# LTC3200-5_Breakout_Board.net
KiCad netlist of a schematic drawn in EAGLE
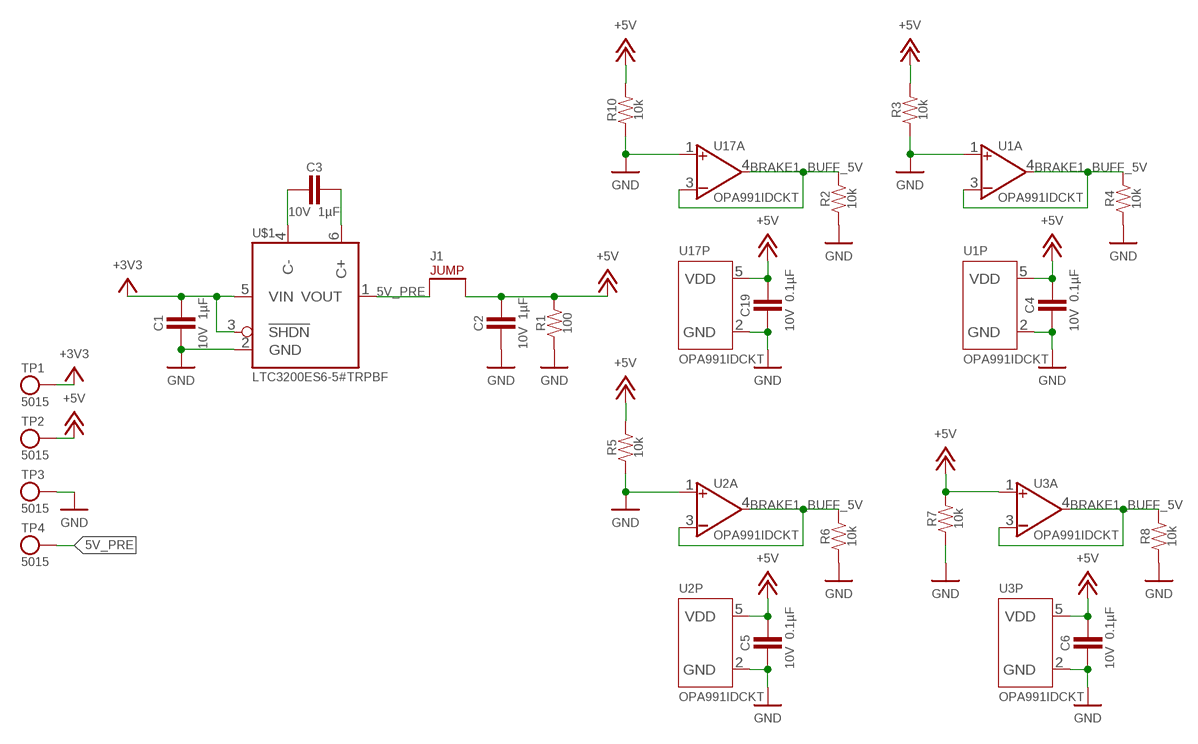
[diagram p0: schematic, sheet 1]

(export (version "E")
  (design (tool "Eeschema 10.0.6"))
  (components
    (comp (ref "C1")
      (value "CAPACITOR_0603_10V_1UF")
      (footprint "eagle-import:0603-CAP")
      (fields
        (field (name "CAPACITANCE") "1µF")
        (field (name "MANUFACTURER") "Yageo")
        (field (name "MPN") "CC0603KRX7R6BB105")
        (field (name "TOLERANCE") "10%")
        (field (name "VOLTAGE") "10V")
      )
      (libsource (lib "eagle-import") (part "CAPACITOR_?_060310V_1UF"))
    )
    (comp (ref "C2")
      (value "CAPACITOR_0603_10V_1UF")
      (footprint "eagle-import:0603-CAP")
      (fields
        (field (name "CAPACITANCE") "1µF")
        (field (name "MANUFACTURER") "Yageo")
        (field (name "MPN") "CC0603KRX7R6BB105")
        (field (name "TOLERANCE") "10%")
        (field (name "VOLTAGE") "10V")
      )
      (libsource (lib "eagle-import") (part "CAPACITOR_?_060310V_1UF"))
    )
    (comp (ref "C3")
      (value "CAPACITOR_0603_10V_1UF")
      (footprint "eagle-import:0603-CAP")
      (fields
        (field (name "CAPACITANCE") "1µF")
        (field (name "MANUFACTURER") "Yageo")
        (field (name "MPN") "CC0603KRX7R6BB105")
        (field (name "TOLERANCE") "10%")
        (field (name "VOLTAGE") "10V")
      )
      (libsource (lib "eagle-import") (part "CAPACITOR_?_060310V_1UF"))
    )
    (comp (ref "C4")
      (value "CAPACITOR_0603_10V_0.1UF")
      (footprint "eagle-import:0603-CAP")
      (fields
        (field (name "CAPACITANCE") "0.1µF")
        (field (name "MANUFACTURER") "Vishay Vitramon")
        (field (name "MPN") "VJ0603Y104JXQPW1BC")
        (field (name "TOLERANCE") "5%")
        (field (name "VOLTAGE") "10V")
      )
      (libsource (lib "eagle-import") (part "CAPACITOR_?_060310V_0.1UF"))
    )
    (comp (ref "C5")
      (value "CAPACITOR_0603_10V_0.1UF")
      (footprint "eagle-import:0603-CAP")
      (fields
        (field (name "CAPACITANCE") "0.1µF")
        (field (name "MANUFACTURER") "Vishay Vitramon")
        (field (name "MPN") "VJ0603Y104JXQPW1BC")
        (field (name "TOLERANCE") "5%")
        (field (name "VOLTAGE") "10V")
      )
      (libsource (lib "eagle-import") (part "CAPACITOR_?_060310V_0.1UF"))
    )
    (comp (ref "C6")
      (value "CAPACITOR_0603_10V_0.1UF")
      (footprint "eagle-import:0603-CAP")
      (fields
        (field (name "CAPACITANCE") "0.1µF")
        (field (name "MANUFACTURER") "Vishay Vitramon")
        (field (name "MPN") "VJ0603Y104JXQPW1BC")
        (field (name "TOLERANCE") "5%")
        (field (name "VOLTAGE") "10V")
      )
      (libsource (lib "eagle-import") (part "CAPACITOR_?_060310V_0.1UF"))
    )
    (comp (ref "C19")
      (value "CAPACITOR_0603_10V_0.1UF")
      (footprint "eagle-import:0603-CAP")
      (fields
        (field (name "CAPACITANCE") "0.1µF")
        (field (name "MANUFACTURER") "Vishay Vitramon")
        (field (name "MPN") "VJ0603Y104JXQPW1BC")
        (field (name "TOLERANCE") "5%")
        (field (name "VOLTAGE") "10V")
      )
      (libsource (lib "eagle-import") (part "CAPACITOR_?_060310V_0.1UF"))
    )
    (comp (ref "J1")
      (value "JUMPER_1X02_")
      (footprint "eagle-import:1X02")
      (libsource (lib "eagle-import") (part "JUMPER_?_1X02"))
    )
    (comp (ref "R1")
      (value "RESISTOR_0603_100")
      (footprint "eagle-import:0603-RES")
      (fields
        (field (name "MANUFACTURER") "Yageo")
        (field (name "MPN") "RC0603FR-07100RL")
        (field (name "POWER") "0.1W")
        (field (name "RESISTANCE") "100")
      )
      (libsource (lib "eagle-import") (part "RESISTOR_?_0603100"))
    )
    (comp (ref "R2")
      (value "RESISTOR_0603_10K")
      (footprint "eagle-import:0603-RES")
      (fields
        (field (name "MANUFACTURER") "Yageo")
        (field (name "MPN") "RC0603FR-0710KL")
        (field (name "POWER") "0.1W")
        (field (name "RESISTANCE") "10k")
      )
      (libsource (lib "eagle-import") (part "RESISTOR_?_060310K"))
    )
    (comp (ref "R3")
      (value "RESISTOR_0603_10K")
      (footprint "eagle-import:0603-RES")
      (fields
        (field (name "MANUFACTURER") "Yageo")
        (field (name "MPN") "RC0603FR-0710KL")
        (field (name "POWER") "0.1W")
        (field (name "RESISTANCE") "10k")
      )
      (libsource (lib "eagle-import") (part "RESISTOR_?_060310K"))
    )
    (comp (ref "R4")
      (value "RESISTOR_0603_10K")
      (footprint "eagle-import:0603-RES")
      (fields
        (field (name "MANUFACTURER") "Yageo")
        (field (name "MPN") "RC0603FR-0710KL")
        (field (name "POWER") "0.1W")
        (field (name "RESISTANCE") "10k")
      )
      (libsource (lib "eagle-import") (part "RESISTOR_?_060310K"))
    )
    (comp (ref "R5")
      (value "RESISTOR_0603_10K")
      (footprint "eagle-import:0603-RES")
      (fields
        (field (name "MANUFACTURER") "Yageo")
        (field (name "MPN") "RC0603FR-0710KL")
        (field (name "POWER") "0.1W")
        (field (name "RESISTANCE") "10k")
      )
      (libsource (lib "eagle-import") (part "RESISTOR_?_060310K"))
    )
    (comp (ref "R6")
      (value "RESISTOR_0603_10K")
      (footprint "eagle-import:0603-RES")
      (fields
        (field (name "MANUFACTURER") "Yageo")
        (field (name "MPN") "RC0603FR-0710KL")
        (field (name "POWER") "0.1W")
        (field (name "RESISTANCE") "10k")
      )
      (libsource (lib "eagle-import") (part "RESISTOR_?_060310K"))
    )
    (comp (ref "R7")
      (value "RESISTOR_0603_10K")
      (footprint "eagle-import:0603-RES")
      (fields
        (field (name "MANUFACTURER") "Yageo")
        (field (name "MPN") "RC0603FR-0710KL")
        (field (name "POWER") "0.1W")
        (field (name "RESISTANCE") "10k")
      )
      (libsource (lib "eagle-import") (part "RESISTOR_?_060310K"))
    )
    (comp (ref "R8")
      (value "RESISTOR_0603_10K")
      (footprint "eagle-import:0603-RES")
      (fields
        (field (name "MANUFACTURER") "Yageo")
        (field (name "MPN") "RC0603FR-0710KL")
        (field (name "POWER") "0.1W")
        (field (name "RESISTANCE") "10k")
      )
      (libsource (lib "eagle-import") (part "RESISTOR_?_060310K"))
    )
    (comp (ref "R10")
      (value "RESISTOR_0603_10K")
      (footprint "eagle-import:0603-RES")
      (fields
        (field (name "MANUFACTURER") "Yageo")
        (field (name "MPN") "RC0603FR-0710KL")
        (field (name "POWER") "0.1W")
        (field (name "RESISTANCE") "10k")
      )
      (libsource (lib "eagle-import") (part "RESISTOR_?_060310K"))
    )
    (comp (ref "TP1")
      (value "TEST_POINT")
      (footprint "eagle-import:MICRO_MINIATURE")
      (fields (field (name "MPN") "5015") (field (name "MANUFACTURER") "Keystone Electronics"))
      (libsource (lib "eagle-import") (part "TEST_POINT"))
    )
    (comp (ref "TP2")
      (value "TEST_POINT")
      (footprint "eagle-import:MICRO_MINIATURE")
      (fields (field (name "MPN") "5015") (field (name "MANUFACTURER") "Keystone Electronics"))
      (libsource (lib "eagle-import") (part "TEST_POINT"))
    )
    (comp (ref "TP3")
      (value "TEST_POINT")
      (footprint "eagle-import:MICRO_MINIATURE")
      (fields (field (name "MPN") "5015") (field (name "MANUFACTURER") "Keystone Electronics"))
      (libsource (lib "eagle-import") (part "TEST_POINT"))
    )
    (comp (ref "TP4")
      (value "TEST_POINT")
      (footprint "eagle-import:MICRO_MINIATURE")
      (fields (field (name "MPN") "5015") (field (name "MANUFACTURER") "Keystone Electronics"))
      (libsource (lib "eagle-import") (part "TEST_POINT"))
    )
    (comp (ref "U$1")
      (value "LTC3200-5")
      (footprint "eagle-import:SOT-23-6")
      (fields (field (name "MPN") "LTC3200ES6-5#TRPBF") (field (name "MANUFACTURER") "Analog Devices Inc."))
      (libsource (lib "eagle-import") (part "LTC3200-5"))
    )
    (comp (ref "U1")
      (value "OPAMP_1_CHANNEL_OPA991")
      (footprint "eagle-import:SC-70-5")
      (fields (field (name "MPN") "OPA991IDCKT"))
      (libsource (lib "eagle-import") (part "OPAMP_1_CHANNEL_OPA991"))
    )
    (comp (ref "U2")
      (value "OPAMP_1_CHANNEL_OPA991")
      (footprint "eagle-import:SC-70-5")
      (fields (field (name "MPN") "OPA991IDCKT"))
      (libsource (lib "eagle-import") (part "OPAMP_1_CHANNEL_OPA991"))
    )
    (comp (ref "U3")
      (value "OPAMP_1_CHANNEL_OPA991")
      (footprint "eagle-import:SC-70-5")
      (fields (field (name "MPN") "OPA991IDCKT"))
      (libsource (lib "eagle-import") (part "OPAMP_1_CHANNEL_OPA991"))
    )
    (comp (ref "U17")
      (value "OPAMP_1_CHANNEL_OPA991")
      (footprint "eagle-import:SC-70-5")
      (fields (field (name "MPN") "OPA991IDCKT"))
      (libsource (lib "eagle-import") (part "OPAMP_1_CHANNEL_OPA991"))
    )
  )
  (nets
    (net (code "1") (name "+3V3") (class "Default")
      (node (ref "C1") (pin "1") (pinfunction "1_1") (pintype "passive"))
      (node (ref "TP1") (pin "1") (pinfunction "P$1_1") (pintype "bidirectional"))
      (node (ref "U$1") (pin "3") (pinfunction "~{SHDN}_3") (pintype "input"))
      (node (ref "U$1") (pin "5") (pinfunction "VIN_5") (pintype "power_in"))
    )
    (net (code "2") (name "+5V") (class "Default")
      (node (ref "C19") (pin "1") (pinfunction "1_1") (pintype "passive"))
      (node (ref "C2") (pin "1") (pinfunction "1_1") (pintype "passive"))
      (node (ref "C4") (pin "1") (pinfunction "1_1") (pintype "passive"))
      (node (ref "C5") (pin "1") (pinfunction "1_1") (pintype "passive"))
      (node (ref "C6") (pin "1") (pinfunction "1_1") (pintype "passive"))
      (node (ref "J1") (pin "2") (pinfunction "P$2_2") (pintype "passive"))
      (node (ref "R1") (pin "2") (pinfunction "2_2") (pintype "passive"))
      (node (ref "R10") (pin "2") (pinfunction "2_2") (pintype "passive"))
      (node (ref "R3") (pin "2") (pinfunction "2_2") (pintype "passive"))
      (node (ref "R5") (pin "2") (pinfunction "2_2") (pintype "passive"))
      (node (ref "R7") (pin "2") (pinfunction "2_2") (pintype "passive"))
      (node (ref "TP2") (pin "1") (pinfunction "P$1_1") (pintype "bidirectional"))
      (node (ref "U1") (pin "5") (pinfunction "VDD_5") (pintype "power_in"))
      (node (ref "U17") (pin "5") (pinfunction "VDD_5") (pintype "power_in"))
      (node (ref "U2") (pin "5") (pinfunction "VDD_5") (pintype "power_in"))
      (node (ref "U3") (pin "1") (pinfunction "VIN+_1") (pintype "input"))
      (node (ref "U3") (pin "5") (pinfunction "VDD_5") (pintype "power_in"))
    )
    (net (code "3") (name "/BRAKE1_BUFF_5V") (class "Default")
      (node (ref "R2") (pin "2") (pinfunction "2_2") (pintype "passive"))
      (node (ref "R4") (pin "2") (pinfunction "2_2") (pintype "passive"))
      (node (ref "R6") (pin "2") (pinfunction "2_2") (pintype "passive"))
      (node (ref "R8") (pin "2") (pinfunction "2_2") (pintype "passive"))
      (node (ref "U1") (pin "3") (pinfunction "VIN-_3") (pintype "input"))
      (node (ref "U1") (pin "4") (pinfunction "VOUT_4") (pintype "output"))
      (node (ref "U17") (pin "3") (pinfunction "VIN-_3") (pintype "input"))
      (node (ref "U17") (pin "4") (pinfunction "VOUT_4") (pintype "output"))
      (node (ref "U2") (pin "3") (pinfunction "VIN-_3") (pintype "input"))
      (node (ref "U2") (pin "4") (pinfunction "VOUT_4") (pintype "output"))
      (node (ref "U3") (pin "3") (pinfunction "VIN-_3") (pintype "input"))
      (node (ref "U3") (pin "4") (pinfunction "VOUT_4") (pintype "output"))
    )
    (net (code "4") (name "5V_PRE") (class "Default")
      (node (ref "J1") (pin "1") (pinfunction "P$1_1") (pintype "passive"))
      (node (ref "TP4") (pin "1") (pinfunction "P$1_1") (pintype "bidirectional"))
      (node (ref "U$1") (pin "1") (pinfunction "VOUT_1") (pintype "power_in"))
    )
    (net (code "5") (name "GND") (class "Default")
      (node (ref "C1") (pin "2") (pinfunction "2_2") (pintype "passive"))
      (node (ref "C19") (pin "2") (pinfunction "2_2") (pintype "passive"))
      (node (ref "C2") (pin "2") (pinfunction "2_2") (pintype "passive"))
      (node (ref "C4") (pin "2") (pinfunction "2_2") (pintype "passive"))
      (node (ref "C5") (pin "2") (pinfunction "2_2") (pintype "passive"))
      (node (ref "C6") (pin "2") (pinfunction "2_2") (pintype "passive"))
      (node (ref "R1") (pin "1") (pinfunction "1_1") (pintype "passive"))
      (node (ref "R10") (pin "1") (pinfunction "1_1") (pintype "passive"))
      (node (ref "R2") (pin "1") (pinfunction "1_1") (pintype "passive"))
      (node (ref "R3") (pin "1") (pinfunction "1_1") (pintype "passive"))
      (node (ref "R4") (pin "1") (pinfunction "1_1") (pintype "passive"))
      (node (ref "R5") (pin "1") (pinfunction "1_1") (pintype "passive"))
      (node (ref "R6") (pin "1") (pinfunction "1_1") (pintype "passive"))
      (node (ref "R7") (pin "1") (pinfunction "1_1") (pintype "passive"))
      (node (ref "R8") (pin "1") (pinfunction "1_1") (pintype "passive"))
      (node (ref "TP3") (pin "1") (pinfunction "P$1_1") (pintype "bidirectional"))
      (node (ref "U$1") (pin "2") (pinfunction "GND_2") (pintype "power_in"))
      (node (ref "U1") (pin "1") (pinfunction "VIN+_1") (pintype "input"))
      (node (ref "U1") (pin "2") (pinfunction "GND_2") (pintype "power_in"))
      (node (ref "U17") (pin "1") (pinfunction "VIN+_1") (pintype "input"))
      (node (ref "U17") (pin "2") (pinfunction "GND_2") (pintype "power_in"))
      (node (ref "U2") (pin "1") (pinfunction "VIN+_1") (pintype "input"))
      (node (ref "U2") (pin "2") (pinfunction "GND_2") (pintype "power_in"))
      (node (ref "U3") (pin "2") (pinfunction "GND_2") (pintype "power_in"))
    )
    (net (code "6") (name "Net-(U$1-C+)") (class "Default")
      (node (ref "C3") (pin "1") (pinfunction "1_1") (pintype "passive"))
      (node (ref "U$1") (pin "6") (pinfunction "C+_6") (pintype "bidirectional"))
    )
    (net (code "7") (name "Net-(U$1-C-)") (class "Default")
      (node (ref "C3") (pin "2") (pinfunction "2_2") (pintype "passive"))
      (node (ref "U$1") (pin "4") (pinfunction "C-_4") (pintype "bidirectional"))
    )
  )
)
